# v0_3_0.net
KiCad netlist of a schematic drawn in EAGLE
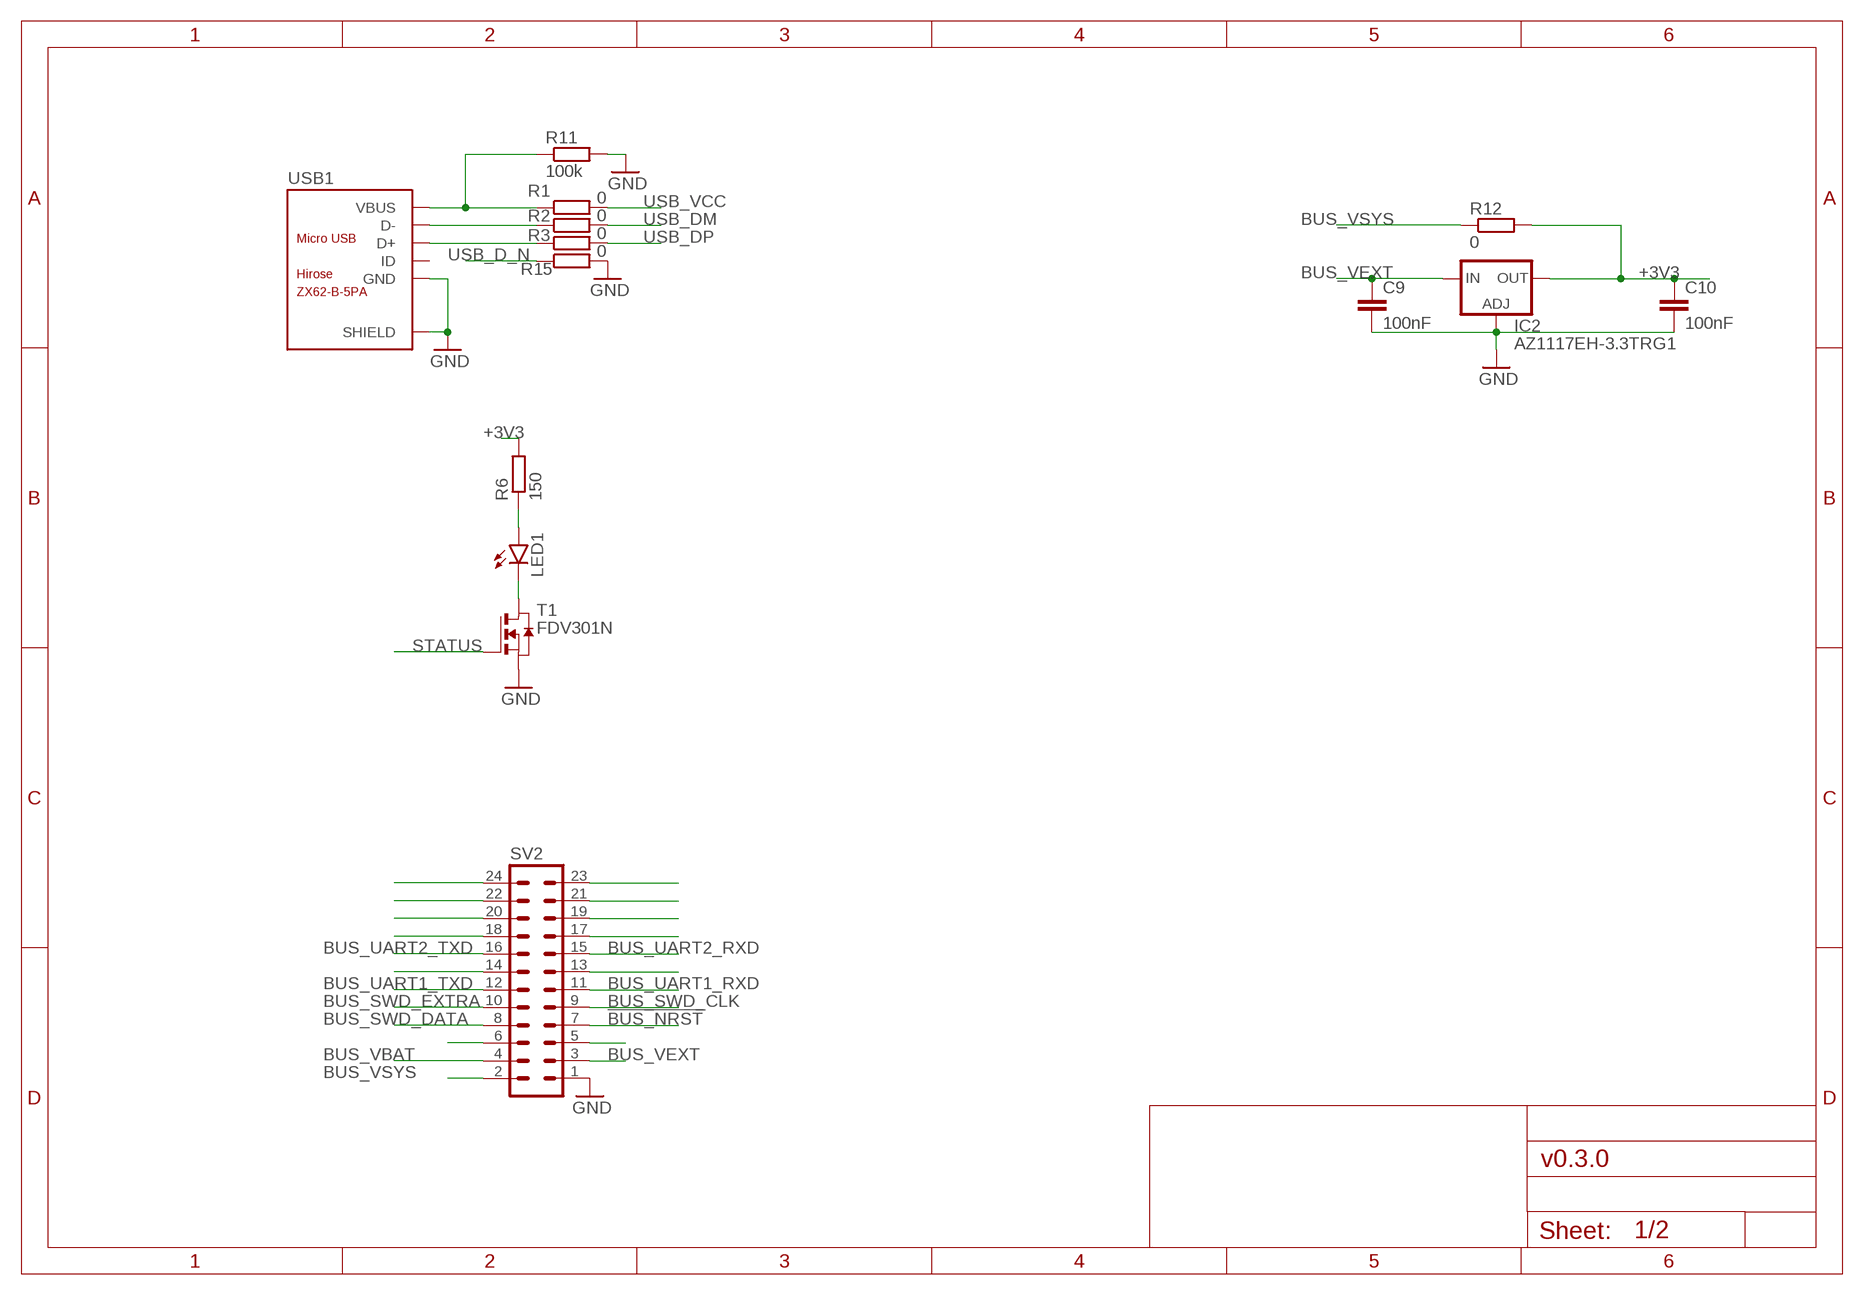
[diagram p0: schematic, sheet 1]
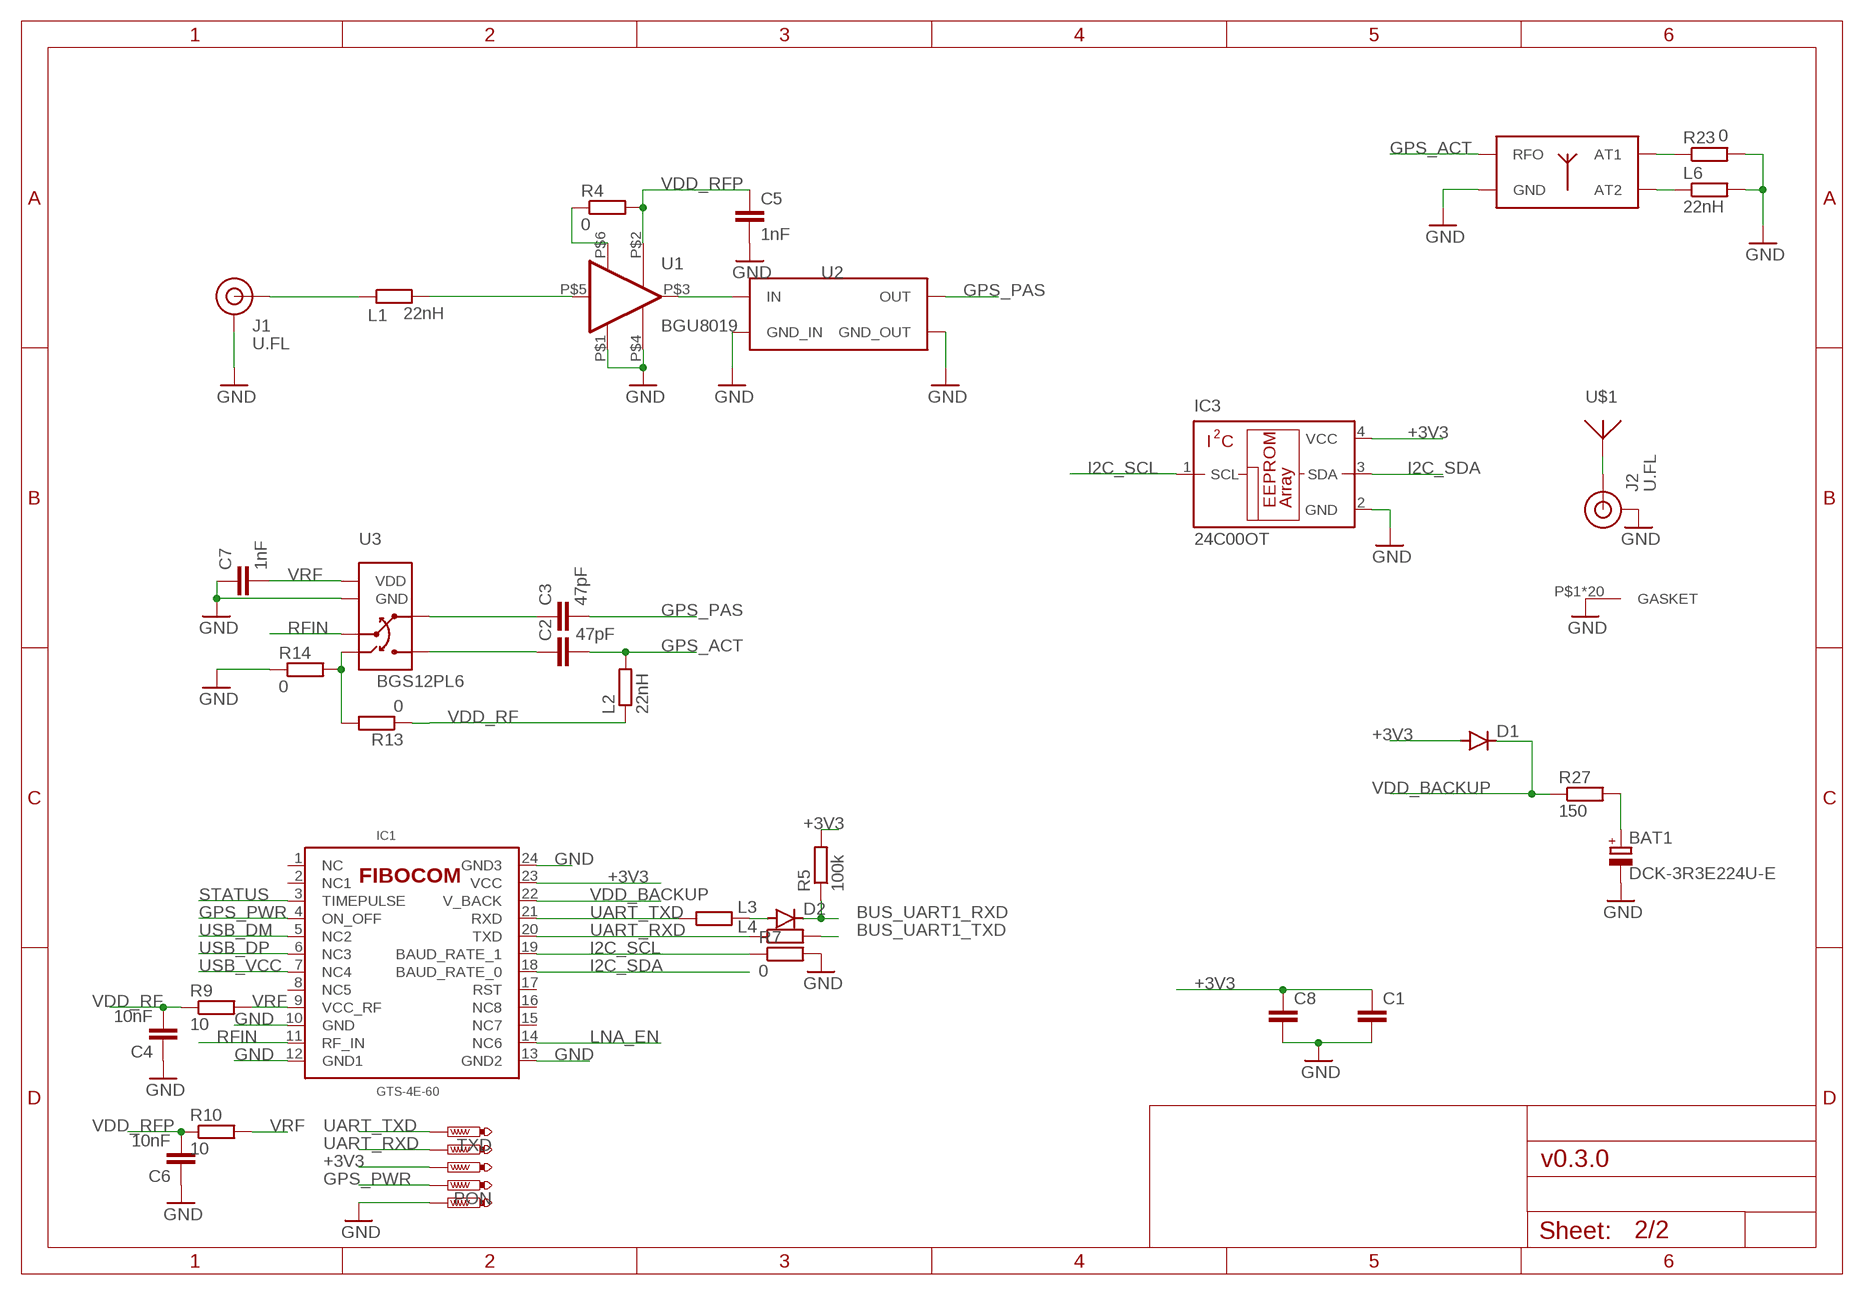
[diagram p1: schematic, sheet 2]

(export (version "E")
  (design (tool "Eeschema 10.0.6"))
  (components
    (comp (ref "C9")
      (value "100nF")
      (footprint "eagle-import:C0603")
      (libsource (lib "eagle-import") (part "C-EUC0603"))
    )
    (comp (ref "C10")
      (value "100nF")
      (footprint "eagle-import:C0603")
      (libsource (lib "eagle-import") (part "C-EUC0603"))
    )
    (comp (ref "IC2")
      (value "AZ1117EH-3.3TRG1")
      (footprint "eagle-import:SOT223")
      (libsource (lib "eagle-import") (part "LD117A?S33TR"))
    )
    (comp (ref "LED1")
      (value "LEDCHIP-LED0603")
      (footprint "eagle-import:CHIP-LED0603")
      (libsource (lib "eagle-import") (part "LEDCHIP-LED0603"))
    )
    (comp (ref "R1")
      (value "0")
      (footprint "eagle-import:R0402")
      (libsource (lib "eagle-import") (part "R-EU_R0402"))
    )
    (comp (ref "R2")
      (value "0")
      (footprint "eagle-import:R0402")
      (libsource (lib "eagle-import") (part "R-EU_R0402"))
    )
    (comp (ref "R3")
      (value "0")
      (footprint "eagle-import:R0402")
      (libsource (lib "eagle-import") (part "R-EU_R0402"))
    )
    (comp (ref "R6")
      (value "150")
      (footprint "eagle-import:R0402")
      (libsource (lib "eagle-import") (part "R-EU_R0402"))
    )
    (comp (ref "R11")
      (value "100k")
      (footprint "eagle-import:R0402")
      (libsource (lib "eagle-import") (part "R-EU_R0402"))
    )
    (comp (ref "R12")
      (value "0")
      (footprint "eagle-import:R0402")
      (libsource (lib "eagle-import") (part "R-EU_R0402"))
    )
    (comp (ref "R15")
      (value "0")
      (footprint "eagle-import:R0402")
      (libsource (lib "eagle-import") (part "R-EU_R0402"))
    )
    (comp (ref "SV2")
      (value "MA12-2")
      (footprint "eagle-import:MA12-2")
      (libsource (lib "eagle-import") (part "MA12-2"))
    )
    (comp (ref "T1")
      (value "FDV301N")
      (footprint "eagle-import:SOT-23")
      (libsource (lib "eagle-import") (part "NMOSSOT23"))
    )
    (comp (ref "USB1")
      (value "ZX62-B-5PA")
      (footprint "eagle-import:MICRO-USB5+6P-SMD-0.65-AB")
      (libsource (lib "eagle-import") (part "MICRO-USB-SMD(ZX62-B-5PA)"))
    )
    (comp (ref "3V3")
      (value "PTR1B1,27")
      (footprint "eagle-import:B1,27")
      (libsource (lib "eagle-import") (part "PTR1B1,27"))
    )
    (comp (ref "ANT1")
      (value "M20047")
      (footprint "eagle-import:PCBCOMPONENT_1")
      (libsource (lib "eagle-import") (part "M20047"))
    )
    (comp (ref "BAT1")
      (value "DCK-3R3E224U-E")
      (footprint "eagle-import:621")
      (libsource (lib "eagle-import") (part "DCK-3R3E224U-E"))
    )
    (comp (ref "C1")
      (value "C-EUC0603")
      (footprint "eagle-import:C0603")
      (libsource (lib "eagle-import") (part "C-EUC0603"))
    )
    (comp (ref "C2")
      (value "47pF")
      (footprint "eagle-import:C0402")
      (libsource (lib "eagle-import") (part "C-EUC0402"))
    )
    (comp (ref "C3")
      (value "47pF")
      (footprint "eagle-import:C0402")
      (libsource (lib "eagle-import") (part "C-EUC0402"))
    )
    (comp (ref "C4")
      (value "10nF")
      (footprint "eagle-import:C0402")
      (libsource (lib "eagle-import") (part "C-EUC0402"))
    )
    (comp (ref "C5")
      (value "1nF")
      (footprint "eagle-import:C0402")
      (libsource (lib "eagle-import") (part "C-EUC0402"))
    )
    (comp (ref "C6")
      (value "10nF")
      (footprint "eagle-import:C0402")
      (libsource (lib "eagle-import") (part "C-EUC0402"))
    )
    (comp (ref "C7")
      (value "1nF")
      (footprint "eagle-import:C0402")
      (libsource (lib "eagle-import") (part "C-EUC0402"))
    )
    (comp (ref "C8")
      (value "C-EUC0402")
      (footprint "eagle-import:C0402")
      (libsource (lib "eagle-import") (part "C-EUC0402"))
    )
    (comp (ref "D1")
      (value "DIODE-SOD323-R")
      (footprint "eagle-import:SOD323-R")
      (libsource (lib "eagle-import") (part "DIODE-SOD323-R"))
    )
    (comp (ref "D2")
      (value "DIODE-SOD323-R")
      (footprint "eagle-import:SOD323-R")
      (libsource (lib "eagle-import") (part "DIODE-SOD323-R"))
    )
    (comp (ref "GND")
      (value "PTR1B1,27")
      (footprint "eagle-import:B1,27")
      (libsource (lib "eagle-import") (part "PTR1B1,27"))
    )
    (comp (ref "IC1")
      (value "GTS-4E-60")
      (footprint "eagle-import:_GTS_4E_60")
      (libsource (lib "eagle-import") (part "GTS-4E-60"))
    )
    (comp (ref "IC3")
      (value "24C00OT")
      (footprint "eagle-import:SOT23-5L")
      (fields (field (name "MF") "MICROCHIP") (field (name "MPN") "24C00T-I/OT"))
      (libsource (lib "eagle-import") (part "2400OTC"))
    )
    (comp (ref "J1")
      (value "U.FL")
      (footprint "eagle-import:U.FL")
      (libsource (lib "eagle-import") (part "U.FL2PIN"))
    )
    (comp (ref "J2")
      (value "U.FL")
      (footprint "eagle-import:U.FL")
      (libsource (lib "eagle-import") (part "U.FL2PIN"))
    )
    (comp (ref "L1")
      (value "22nH")
      (footprint "eagle-import:R0402")
      (libsource (lib "eagle-import") (part "R-EU_R0402"))
    )
    (comp (ref "L2")
      (value "22nH")
      (footprint "eagle-import:R0402")
      (libsource (lib "eagle-import") (part "R-EU_R0402"))
    )
    (comp (ref "L3")
      (value "R-EU_R0402")
      (footprint "eagle-import:R0402")
      (libsource (lib "eagle-import") (part "R-EU_R0402"))
    )
    (comp (ref "L4")
      (value "R-EU_R0402")
      (footprint "eagle-import:R0402")
      (libsource (lib "eagle-import") (part "R-EU_R0402"))
    )
    (comp (ref "L6")
      (value "22nH")
      (footprint "eagle-import:R0402")
      (libsource (lib "eagle-import") (part "R-EU_R0402"))
    )
    (comp (ref "PON")
      (value "PTR1B1,27")
      (footprint "eagle-import:B1,27")
      (libsource (lib "eagle-import") (part "PTR1B1,27"))
    )
    (comp (ref "R4")
      (value "0")
      (footprint "eagle-import:R0402")
      (libsource (lib "eagle-import") (part "R-EU_R0402"))
    )
    (comp (ref "R5")
      (value "100k")
      (footprint "eagle-import:R0402")
      (libsource (lib "eagle-import") (part "R-EU_R0402"))
    )
    (comp (ref "R7")
      (value "0")
      (footprint "eagle-import:R0402")
      (libsource (lib "eagle-import") (part "R-EU_R0402"))
    )
    (comp (ref "R9")
      (value "10")
      (footprint "eagle-import:R0402")
      (libsource (lib "eagle-import") (part "R-EU_R0402"))
    )
    (comp (ref "R10")
      (value "10")
      (footprint "eagle-import:R0402")
      (libsource (lib "eagle-import") (part "R-EU_R0402"))
    )
    (comp (ref "R13")
      (value "0")
      (footprint "eagle-import:R0402")
      (libsource (lib "eagle-import") (part "R-EU_R0402"))
    )
    (comp (ref "R14")
      (value "0")
      (footprint "eagle-import:R0402")
      (libsource (lib "eagle-import") (part "R-EU_R0402"))
    )
    (comp (ref "R23")
      (value "0")
      (footprint "eagle-import:R0402")
      (libsource (lib "eagle-import") (part "R-EU_R0402"))
    )
    (comp (ref "R27")
      (value "150")
      (footprint "eagle-import:R0402")
      (libsource (lib "eagle-import") (part "R-EU_R0402"))
    )
    (comp (ref "RXD")
      (value "PTR1B1,27")
      (footprint "eagle-import:B1,27")
      (libsource (lib "eagle-import") (part "PTR1B1,27"))
    )
    (comp (ref "TXD")
      (value "PTR1B1,27")
      (footprint "eagle-import:B1,27")
      (libsource (lib "eagle-import") (part "PTR1B1,27"))
    )
    (comp (ref "U$1")
      (value "ANT1590-2540A")
      (footprint "eagle-import:2540A")
      (libsource (lib "eagle-import") (part "ANT1590-2540A"))
    )
    (comp (ref "U$2")
      (value "2118718-2")
      (footprint "eagle-import:2118717-2")
      (libsource (lib "eagle-import") (part "2118718-2"))
    )
    (comp (ref "U1")
      (value "BGU8019")
      (footprint "eagle-import:XSON6")
      (libsource (lib "eagle-import") (part "BGU8019"))
    )
    (comp (ref "U2")
      (value "B3916B8813P810")
      (footprint "eagle-import:XSON5")
      (libsource (lib "eagle-import") (part "B3916B8813P810"))
    )
    (comp (ref "U3")
      (value "BGS12PL6")
      (footprint "eagle-import:TSLP-6-4")
      (libsource (lib "eagle-import") (part "BGS12PL6"))
    )
  )
  (nets
    (net (code "1") (name "+3V3") (class "Default")
      (node (ref "3V3") (pin "TP") (pinfunction "TP_TP") (pintype "input"))
      (node (ref "C1") (pin "1") (pinfunction "1_1") (pintype "passive"))
      (node (ref "C10") (pin "1") (pinfunction "1_1") (pintype "passive"))
      (node (ref "C8") (pin "1") (pinfunction "1_1") (pintype "passive"))
      (node (ref "D1") (pin "A") (pinfunction "A_A") (pintype "passive"))
      (node (ref "IC1") (pin "23") (pinfunction "VCC_23") (pintype "bidirectional"))
      (node (ref "IC2") (pin "4") (pinfunction "OUT_4") (pintype "passive"))
      (node (ref "IC3") (pin "4") (pinfunction "VCC_4") (pintype "power_in"))
      (node (ref "R12") (pin "2") (pinfunction "2_2") (pintype "passive"))
      (node (ref "R5") (pin "2") (pinfunction "2_2") (pintype "passive"))
      (node (ref "R6") (pin "2") (pinfunction "2_2") (pintype "passive"))
    )
    (net (code "2") (name "BUS_SWD_CLK") (class "Default")
      (node (ref "SV2") (pin "9") (pinfunction "9_9") (pintype "passive"))
    )
    (net (code "3") (name "BUS_SWD_DATA") (class "Default")
      (node (ref "SV2") (pin "8") (pinfunction "8_8") (pintype "passive"))
    )
    (net (code "4") (name "BUS_SWD_EXTRA") (class "Default")
      (node (ref "SV2") (pin "10") (pinfunction "10_10") (pintype "passive"))
    )
    (net (code "5") (name "BUS_UART1_RXD") (class "Default")
      (node (ref "D2") (pin "C") (pinfunction "C_C") (pintype "passive"))
      (node (ref "R5") (pin "1") (pinfunction "1_1") (pintype "passive"))
      (node (ref "SV2") (pin "11") (pinfunction "11_11") (pintype "passive"))
    )
    (net (code "6") (name "BUS_UART1_TXD") (class "Default")
      (node (ref "L4") (pin "2") (pinfunction "2_2") (pintype "passive"))
      (node (ref "SV2") (pin "12") (pinfunction "12_12") (pintype "passive"))
    )
    (net (code "7") (name "BUS_UART2_RXD") (class "Default")
      (node (ref "SV2") (pin "15") (pinfunction "15_15") (pintype "passive"))
    )
    (net (code "8") (name "BUS_UART2_TXD") (class "Default")
      (node (ref "SV2") (pin "16") (pinfunction "16_16") (pintype "passive"))
    )
    (net (code "9") (name "BUS_VBAT") (class "Default")
      (node (ref "SV2") (pin "4") (pinfunction "4_4") (pintype "passive"))
    )
    (net (code "10") (name "BUS_VEXT") (class "Default")
      (node (ref "C9") (pin "1") (pinfunction "1_1") (pintype "passive"))
      (node (ref "IC2") (pin "3") (pinfunction "IN_3") (pintype "input"))
      (node (ref "SV2") (pin "3") (pinfunction "3_3") (pintype "passive"))
    )
    (net (code "11") (name "BUS_VSYS") (class "Default")
      (node (ref "R12") (pin "1") (pinfunction "1_1") (pintype "passive"))
      (node (ref "SV2") (pin "2") (pinfunction "2_2") (pintype "passive"))
    )
    (net (code "12") (name "GND") (class "Default")
      (node (ref "ANT1") (pin "2") (pinfunction "GND_2") (pintype "power_in"))
      (node (ref "ANT1") (pin "3") (pinfunction "GND_3") (pintype "power_in"))
      (node (ref "ANT1") (pin "4") (pinfunction "GND_4") (pintype "power_in"))
      (node (ref "BAT1") (pin "-") (pinfunction "-_-") (pintype "passive"))
      (node (ref "C1") (pin "2") (pinfunction "2_2") (pintype "passive"))
      (node (ref "C10") (pin "2") (pinfunction "2_2") (pintype "passive"))
      (node (ref "C4") (pin "1") (pinfunction "1_1") (pintype "passive"))
      (node (ref "C5") (pin "2") (pinfunction "2_2") (pintype "passive"))
      (node (ref "C6") (pin "1") (pinfunction "1_1") (pintype "passive"))
      (node (ref "C7") (pin "1") (pinfunction "1_1") (pintype "passive"))
      (node (ref "C8") (pin "2") (pinfunction "2_2") (pintype "passive"))
      (node (ref "C9") (pin "2") (pinfunction "2_2") (pintype "passive"))
      (node (ref "GND") (pin "TP") (pinfunction "TP_TP") (pintype "input"))
      (node (ref "IC1") (pin "10") (pinfunction "GND_10") (pintype "bidirectional"))
      (node (ref "IC1") (pin "12") (pinfunction "GND1_12") (pintype "bidirectional"))
      (node (ref "IC1") (pin "13") (pinfunction "GND2_13") (pintype "bidirectional"))
      (node (ref "IC1") (pin "24") (pinfunction "GND3_24") (pintype "bidirectional"))
      (node (ref "IC2") (pin "1") (pinfunction "ADJ_1") (pintype "input"))
      (node (ref "IC3") (pin "2") (pinfunction "GND_2") (pintype "power_in"))
      (node (ref "J1") (pin "1") (pinfunction "GND_1") (pintype "bidirectional"))
      (node (ref "J1") (pin "2") (pinfunction "GND_2") (pintype "bidirectional"))
      (node (ref "J2") (pin "1") (pinfunction "GND_1") (pintype "bidirectional"))
      (node (ref "J2") (pin "2") (pinfunction "GND_2") (pintype "bidirectional"))
      (node (ref "L6") (pin "2") (pinfunction "2_2") (pintype "passive"))
      (node (ref "R11") (pin "2") (pinfunction "2_2") (pintype "passive"))
      (node (ref "R14") (pin "1") (pinfunction "1_1") (pintype "passive"))
      (node (ref "R15") (pin "2") (pinfunction "2_2") (pintype "passive"))
      (node (ref "R23") (pin "2") (pinfunction "2_2") (pintype "passive"))
      (node (ref "R7") (pin "2") (pinfunction "2_2") (pintype "passive"))
      (node (ref "SV2") (pin "1") (pinfunction "1_1") (pintype "passive"))
      (node (ref "T1") (pin "2") (pinfunction "S_2") (pintype "passive"))
      (node (ref "U$2") (pin "P$1") (pinfunction "GASKET_P$1") (pintype "bidirectional"))
      (node (ref "U$2") (pin "P$10") (pinfunction "GASKET_P$10") (pintype "bidirectional"))
      (node (ref "U$2") (pin "P$11") (pinfunction "GASKET_P$11") (pintype "bidirectional"))
      (node (ref "U$2") (pin "P$12") (pinfunction "GASKET_P$12") (pintype "bidirectional"))
      (node (ref "U$2") (pin "P$13") (pinfunction "GASKET_P$13") (pintype "bidirectional"))
      (node (ref "U$2") (pin "P$14") (pinfunction "GASKET_P$14") (pintype "bidirectional"))
      (node (ref "U$2") (pin "P$15") (pinfunction "GASKET_P$15") (pintype "bidirectional"))
      (node (ref "U$2") (pin "P$16") (pinfunction "GASKET_P$16") (pintype "bidirectional"))
      (node (ref "U$2") (pin "P$17") (pinfunction "GASKET_P$17") (pintype "bidirectional"))
      (node (ref "U$2") (pin "P$18") (pinfunction "GASKET_P$18") (pintype "bidirectional"))
      (node (ref "U$2") (pin "P$19") (pinfunction "GASKET_P$19") (pintype "bidirectional"))
      (node (ref "U$2") (pin "P$2") (pinfunction "GASKET_P$2") (pintype "bidirectional"))
      (node (ref "U$2") (pin "P$20") (pinfunction "GASKET_P$20") (pintype "bidirectional"))
      (node (ref "U$2") (pin "P$3") (pinfunction "GASKET_P$3") (pintype "bidirectional"))
      (node (ref "U$2") (pin "P$4") (pinfunction "GASKET_P$4") (pintype "bidirectional"))
      (node (ref "U$2") (pin "P$5") (pinfunction "GASKET_P$5") (pintype "bidirectional"))
      (node (ref "U$2") (pin "P$6") (pinfunction "GASKET_P$6") (pintype "bidirectional"))
      (node (ref "U$2") (pin "P$7") (pinfunction "GASKET_P$7") (pintype "bidirectional"))
      (node (ref "U$2") (pin "P$8") (pinfunction "GASKET_P$8") (pintype "bidirectional"))
      (node (ref "U$2") (pin "P$9") (pinfunction "GASKET_P$9") (pintype "bidirectional"))
      (node (ref "U1") (pin "P$1") (pinfunction "GND_P$1") (pintype "power_in"))
      (node (ref "U1") (pin "P$4") (pinfunction "GND_RF_P$4") (pintype "passive"))
      (node (ref "U2") (pin "2") (pinfunction "GND_IN_2") (pintype "bidirectional"))
      (node (ref "U2") (pin "3") (pinfunction "GND_OUT_3") (pintype "bidirectional"))
      (node (ref "U2") (pin "5") (pinfunction "GND_IN_5") (pintype "bidirectional"))
      (node (ref "U3") (pin "P$2") (pinfunction "GND_P$2") (pintype "power_in"))
      (node (ref "USB1") (pin "5") (pinfunction "GND_5") (pintype "power_in"))
      (node (ref "USB1") (pin "P1") (pinfunction "SHIELD_P1") (pintype "power_in"))
      (node (ref "USB1") (pin "P2") (pinfunction "SHIELD_P2") (pintype "power_in"))
      (node (ref "USB1") (pin "P3") (pinfunction "SHIELD_P3") (pintype "power_in"))
      (node (ref "USB1") (pin "P4") (pinfunction "SHIELD_P4") (pintype "power_in"))
      (node (ref "USB1") (pin "P5") (pinfunction "SHIELD_P5") (pintype "power_in"))
      (node (ref "USB1") (pin "P6") (pinfunction "SHIELD_P6") (pintype "power_in"))
    )
    (net (code "13") (name "GPS_ACT") (class "Default")
      (node (ref "ANT1") (pin "5") (pinfunction "RFO_5") (pintype "input"))
      (node (ref "C2") (pin "2") (pinfunction "2_2") (pintype "passive"))
      (node (ref "L2") (pin "2") (pinfunction "2_2") (pintype "passive"))
    )
    (net (code "14") (name "GPS_PAS") (class "Default")
      (node (ref "C3") (pin "2") (pinfunction "2_2") (pintype "passive"))
      (node (ref "U2") (pin "4") (pinfunction "OUT_4") (pintype "bidirectional"))
    )
    (net (code "15") (name "GPS_PWR") (class "Default")
      (node (ref "IC1") (pin "4") (pinfunction "ON_OFF_4") (pintype "bidirectional"))
      (node (ref "PON") (pin "TP") (pinfunction "TP_TP") (pintype "input"))
    )
    (net (code "16") (name "I2C_SCL") (class "Default")
      (node (ref "IC1") (pin "19") (pinfunction "BAUD_RATE_1_19") (pintype "bidirectional"))
      (node (ref "IC3") (pin "1") (pinfunction "SCL_1") (pintype "input"))
      (node (ref "R7") (pin "1") (pinfunction "1_1") (pintype "passive"))
    )
    (net (code "17") (name "I2C_SDA") (class "Default")
      (node (ref "IC1") (pin "18") (pinfunction "BAUD_RATE_0_18") (pintype "bidirectional"))
      (node (ref "IC3") (pin "3") (pinfunction "SDA_3") (pintype "bidirectional"))
    )
    (net (code "18") (name "LNA_EN") (class "Default")
      (node (ref "IC1") (pin "14") (pinfunction "NC6_14") (pintype "bidirectional"))
    )
    (net (code "19") (name "Net-(ANT1-AT1)") (class "Default")
      (node (ref "ANT1") (pin "1") (pinfunction "AT1_1") (pintype "bidirectional"))
      (node (ref "R23") (pin "1") (pinfunction "1_1") (pintype "passive"))
    )
    (net (code "20") (name "Net-(ANT1-AT2)") (class "Default")
      (node (ref "ANT1") (pin "6") (pinfunction "AT2_6") (pintype "bidirectional"))
      (node (ref "L6") (pin "1") (pinfunction "1_1") (pintype "passive"))
    )
    (net (code "21") (name "Net-(BAT1-Pad+)") (class "Default")
      (node (ref "BAT1") (pin "+") (pinfunction "+_+") (pintype "passive"))
      (node (ref "R27") (pin "2") (pinfunction "2_2") (pintype "passive"))
    )
    (net (code "22") (name "Net-(D2-PadA)") (class "Default")
      (node (ref "D2") (pin "A") (pinfunction "A_A") (pintype "passive"))
      (node (ref "L3") (pin "2") (pinfunction "2_2") (pintype "passive"))
    )
    (net (code "23") (name "Net-(J1-SIGNAL)") (class "Default")
      (node (ref "J1") (pin "FEED") (pinfunction "SIGNAL_FEED") (pintype "bidirectional"))
      (node (ref "L1") (pin "1") (pinfunction "1_1") (pintype "passive"))
    )
    (net (code "24") (name "Net-(J2-SIGNAL)") (class "Default")
      (node (ref "J2") (pin "FEED") (pinfunction "SIGNAL_FEED") (pintype "bidirectional"))
      (node (ref "U$1") (pin "P$1") (pinfunction "P$1_P$1") (pintype "bidirectional"))
    )
    (net (code "25") (name "Net-(LED1-PadA)") (class "Default")
      (node (ref "LED1") (pin "A") (pinfunction "A_A") (pintype "passive"))
      (node (ref "R6") (pin "1") (pinfunction "1_1") (pintype "passive"))
    )
    (net (code "26") (name "Net-(T1-D)") (class "Default")
      (node (ref "LED1") (pin "C") (pinfunction "C_C") (pintype "passive"))
      (node (ref "T1") (pin "1") (pinfunction "D_1") (pintype "passive"))
    )
    (net (code "27") (name "Net-(U1-ENABLE)") (class "Default")
      (node (ref "R4") (pin "1") (pinfunction "1_1") (pintype "passive"))
      (node (ref "U1") (pin "P$6") (pinfunction "ENABLE_P$6") (pintype "power_in"))
    )
    (net (code "28") (name "Net-(U1-RF_IN)") (class "Default")
      (node (ref "L1") (pin "2") (pinfunction "2_2") (pintype "passive"))
      (node (ref "U1") (pin "P$5") (pinfunction "RF_IN_P$5") (pintype "input"))
    )
    (net (code "29") (name "Net-(U1-RF_OUT)") (class "Default")
      (node (ref "U1") (pin "P$3") (pinfunction "RF_OUT_P$3") (pintype "output"))
      (node (ref "U2") (pin "1") (pinfunction "IN_1") (pintype "bidirectional"))
    )
    (net (code "30") (name "Net-(U3-P$4)") (class "Default")
      (node (ref "R13") (pin "2") (pinfunction "2_2") (pintype "passive"))
      (node (ref "R14") (pin "2") (pinfunction "2_2") (pintype "passive"))
      (node (ref "U3") (pin "P$6") (pinfunction "P$4_P$6") (pintype "bidirectional"))
    )
    (net (code "31") (name "Net-(U3-RF1)") (class "Default")
      (node (ref "C3") (pin "1") (pinfunction "1_1") (pintype "passive"))
      (node (ref "U3") (pin "P$3") (pinfunction "RF1_P$3") (pintype "bidirectional"))
    )
    (net (code "32") (name "Net-(U3-RF2)") (class "Default")
      (node (ref "C2") (pin "1") (pinfunction "1_1") (pintype "passive"))
      (node (ref "U3") (pin "P$1") (pinfunction "RF2_P$1") (pintype "bidirectional"))
    )
    (net (code "33") (name "Net-(USB1-D+)") (class "Default")
      (node (ref "R3") (pin "1") (pinfunction "1_1") (pintype "passive"))
      (node (ref "USB1") (pin "3") (pinfunction "D+_3") (pintype "bidirectional"))
    )
    (net (code "34") (name "Net-(USB1-VBUS)") (class "Default")
      (node (ref "R1") (pin "1") (pinfunction "1_1") (pintype "passive"))
      (node (ref "R11") (pin "1") (pinfunction "1_1") (pintype "passive"))
      (node (ref "USB1") (pin "1") (pinfunction "VBUS_1") (pintype "power_in"))
    )
    (net (code "35") (name "RFIN") (class "Default")
      (node (ref "IC1") (pin "11") (pinfunction "RF_IN_11") (pintype "bidirectional"))
      (node (ref "U3") (pin "P$5") (pinfunction "RFIN_P$5") (pintype "bidirectional"))
    )
    (net (code "36") (name "STATUS") (class "Default")
      (node (ref "IC1") (pin "3") (pinfunction "TIMEPULSE_3") (pintype "bidirectional"))
      (node (ref "T1") (pin "3") (pinfunction "G_3") (pintype "passive"))
    )
    (net (code "37") (name "UART_RXD") (class "Default")
      (node (ref "IC1") (pin "20") (pinfunction "TXD_20") (pintype "bidirectional"))
      (node (ref "L4") (pin "1") (pinfunction "1_1") (pintype "passive"))
      (node (ref "RXD") (pin "TP") (pinfunction "TP_TP") (pintype "input"))
    )
    (net (code "38") (name "UART_TXD") (class "Default")
      (node (ref "IC1") (pin "21") (pinfunction "RXD_21") (pintype "bidirectional"))
      (node (ref "L3") (pin "1") (pinfunction "1_1") (pintype "passive"))
      (node (ref "TXD") (pin "TP") (pinfunction "TP_TP") (pintype "input"))
    )
    (net (code "39") (name "USB_DM") (class "Default")
      (node (ref "IC1") (pin "5") (pinfunction "NC2_5") (pintype "bidirectional"))
      (node (ref "R2") (pin "2") (pinfunction "2_2") (pintype "passive"))
    )
    (net (code "40") (name "USB_DP") (class "Default")
      (node (ref "IC1") (pin "6") (pinfunction "NC3_6") (pintype "bidirectional"))
      (node (ref "R3") (pin "2") (pinfunction "2_2") (pintype "passive"))
    )
    (net (code "41") (name "USB_D_N") (class "Default")
      (node (ref "R15") (pin "1") (pinfunction "1_1") (pintype "passive"))
      (node (ref "R2") (pin "1") (pinfunction "1_1") (pintype "passive"))
      (node (ref "USB1") (pin "2") (pinfunction "D-_2") (pintype "bidirectional"))
    )
    (net (code "42") (name "USB_VCC") (class "Default")
      (node (ref "IC1") (pin "7") (pinfunction "NC4_7") (pintype "bidirectional"))
      (node (ref "R1") (pin "2") (pinfunction "2_2") (pintype "passive"))
    )
    (net (code "43") (name "VDD_BACKUP") (class "Default")
      (node (ref "D1") (pin "C") (pinfunction "C_C") (pintype "passive"))
      (node (ref "IC1") (pin "22") (pinfunction "V_BACK_22") (pintype "bidirectional"))
      (node (ref "R27") (pin "1") (pinfunction "1_1") (pintype "passive"))
    )
    (net (code "44") (name "VDD_RF") (class "Default")
      (node (ref "C4") (pin "2") (pinfunction "2_2") (pintype "passive"))
      (node (ref "L2") (pin "1") (pinfunction "1_1") (pintype "passive"))
      (node (ref "R13") (pin "1") (pinfunction "1_1") (pintype "passive"))
      (node (ref "R9") (pin "1") (pinfunction "1_1") (pintype "passive"))
    )
    (net (code "45") (name "VDD_RFP") (class "Default")
      (node (ref "C5") (pin "1") (pinfunction "1_1") (pintype "passive"))
      (node (ref "C6") (pin "2") (pinfunction "2_2") (pintype "passive"))
      (node (ref "R10") (pin "1") (pinfunction "1_1") (pintype "passive"))
      (node (ref "R4") (pin "2") (pinfunction "2_2") (pintype "passive"))
      (node (ref "U1") (pin "P$2") (pinfunction "VCC_P$2") (pintype "passive"))
    )
    (net (code "46") (name "VRF") (class "Default")
      (node (ref "C7") (pin "2") (pinfunction "2_2") (pintype "passive"))
      (node (ref "IC1") (pin "9") (pinfunction "VCC_RF_9") (pintype "bidirectional"))
      (node (ref "R10") (pin "2") (pinfunction "2_2") (pintype "passive"))
      (node (ref "R9") (pin "2") (pinfunction "2_2") (pintype "passive"))
      (node (ref "U3") (pin "P$4") (pinfunction "VDD_P$4") (pintype "power_in"))
    )
    (net (code "47") (name "unconnected-(IC1-NC-Pad1)") (class "Default")
      (node (ref "IC1") (pin "1") (pinfunction "NC_1") (pintype "bidirectional"))
    )
    (net (code "48") (name "unconnected-(IC1-NC1-Pad2)") (class "Default")
      (node (ref "IC1") (pin "2") (pinfunction "NC1_2") (pintype "bidirectional"))
    )
    (net (code "49") (name "unconnected-(IC1-NC5-Pad8)") (class "Default")
      (node (ref "IC1") (pin "8") (pinfunction "NC5_8") (pintype "bidirectional"))
    )
    (net (code "50") (name "unconnected-(IC1-NC7-Pad15)") (class "Default")
      (node (ref "IC1") (pin "15") (pinfunction "NC7_15") (pintype "bidirectional"))
    )
    (net (code "51") (name "unconnected-(IC1-NC8-Pad16)") (class "Default")
      (node (ref "IC1") (pin "16") (pinfunction "NC8_16") (pintype "bidirectional"))
    )
    (net (code "52") (name "unconnected-(IC1-RST-Pad17)") (class "Default")
      (node (ref "IC1") (pin "17") (pinfunction "RST_17") (pintype "bidirectional"))
    )
    (net (code "53") (name "unconnected-(SV2-Pad5)") (class "Default")
      (node (ref "SV2") (pin "5") (pinfunction "5_5") (pintype "passive"))
    )
    (net (code "54") (name "unconnected-(SV2-Pad6)") (class "Default")
      (node (ref "SV2") (pin "6") (pinfunction "6_6") (pintype "passive"))
    )
    (net (code "55") (name "unconnected-(SV2-Pad13)") (class "Default")
      (node (ref "SV2") (pin "13") (pinfunction "13_13") (pintype "passive"))
    )
    (net (code "56") (name "unconnected-(SV2-Pad14)") (class "Default")
      (node (ref "SV2") (pin "14") (pinfunction "14_14") (pintype "passive"))
    )
    (net (code "57") (name "unconnected-(SV2-Pad17)") (class "Default")
      (node (ref "SV2") (pin "17") (pinfunction "17_17") (pintype "passive"))
    )
    (net (code "58") (name "unconnected-(SV2-Pad18)") (class "Default")
      (node (ref "SV2") (pin "18") (pinfunction "18_18") (pintype "passive"))
    )
    (net (code "59") (name "unconnected-(SV2-Pad19)") (class "Default")
      (node (ref "SV2") (pin "19") (pinfunction "19_19") (pintype "passive"))
    )
    (net (code "60") (name "unconnected-(SV2-Pad20)") (class "Default")
      (node (ref "SV2") (pin "20") (pinfunction "20_20") (pintype "passive"))
    )
    (net (code "61") (name "unconnected-(SV2-Pad21)") (class "Default")
      (node (ref "SV2") (pin "21") (pinfunction "21_21") (pintype "passive"))
    )
    (net (code "62") (name "unconnected-(SV2-Pad22)") (class "Default")
      (node (ref "SV2") (pin "22") (pinfunction "22_22") (pintype "passive"))
    )
    (net (code "63") (name "unconnected-(SV2-Pad23)") (class "Default")
      (node (ref "SV2") (pin "23") (pinfunction "23_23") (pintype "passive"))
    )
    (net (code "64") (name "unconnected-(SV2-Pad24)") (class "Default")
      (node (ref "SV2") (pin "24") (pinfunction "24_24") (pintype "passive"))
    )
    (net (code "65") (name "unconnected-(USB1-ID-Pad4)") (class "Default")
      (node (ref "USB1") (pin "4") (pinfunction "ID_4") (pintype "bidirectional"))
    )
    (net (code "66") (name "~{BUS_NRST}") (class "Default")
      (node (ref "SV2") (pin "7") (pinfunction "7_7") (pintype "passive"))
    )
  )
)
